# Display.net
KiCad netlist of a schematic drawn in Altium Designer
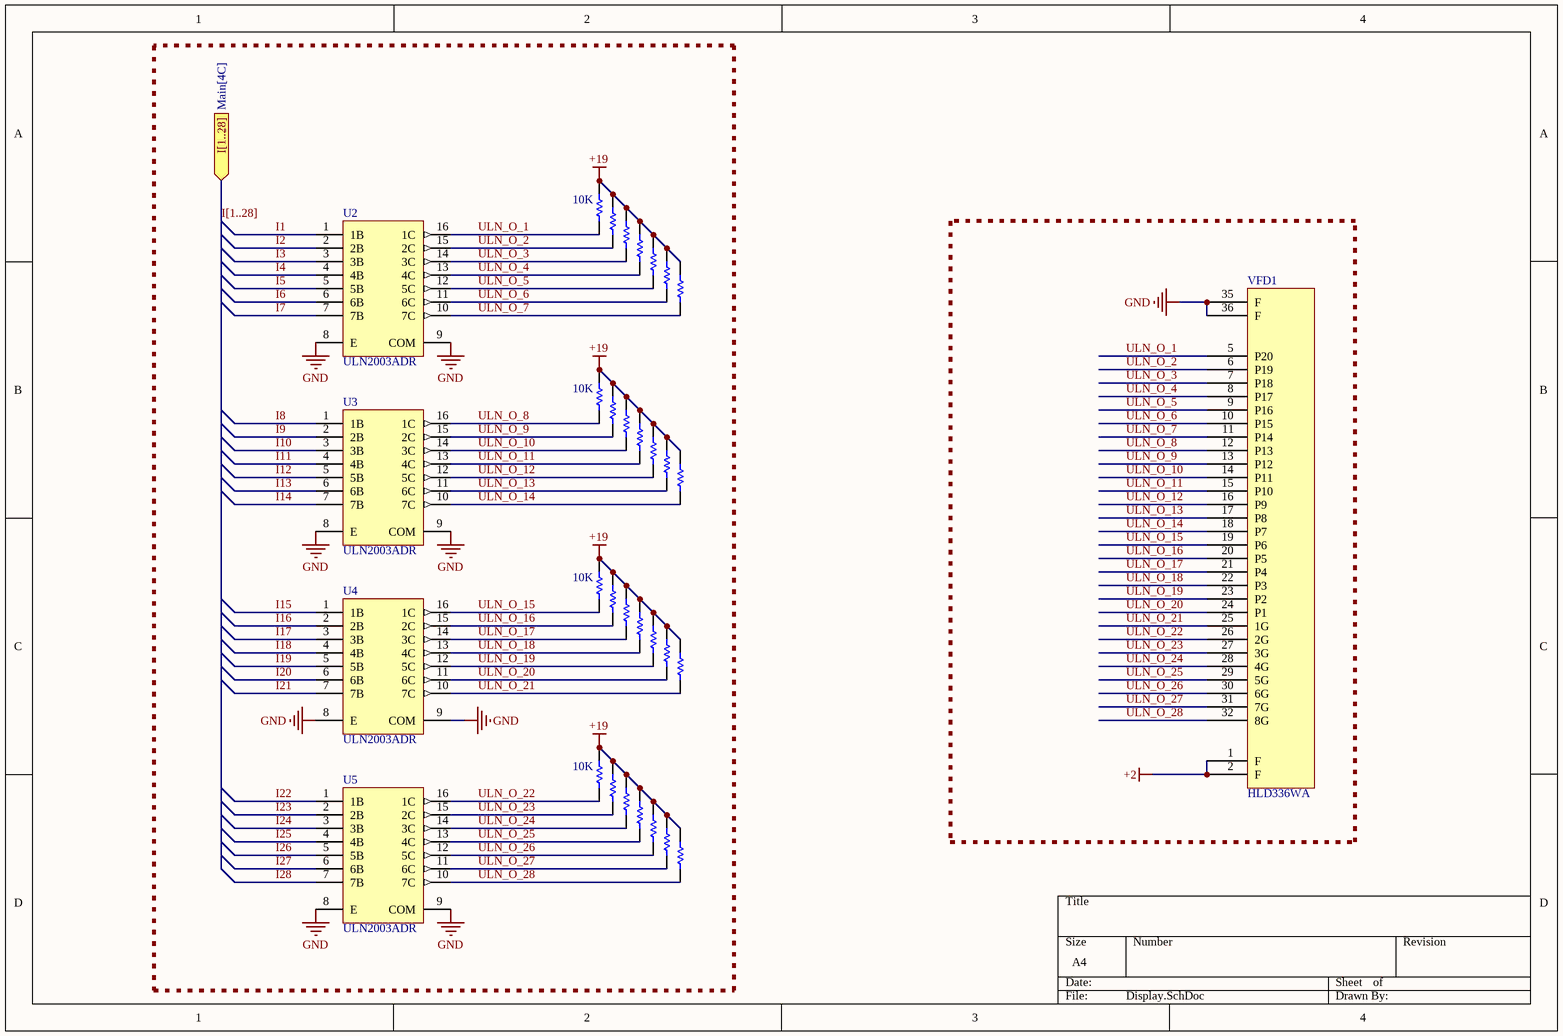
[diagram p0: Display.SchDoc]

(export (version "E")
  (design (tool "Eeschema 10.0.6"))
  (components
    (comp (ref "R4")
      (value "10K")
      (footprint "RESC1609X50X30ML10T20")
      (fields (field (name "MANUFACTURER") "Vishay Dale") (field (name "PART NUMBER") "CRCW060310K0FKTB"))
      (libsource (lib "Altium Content Vault") (part "RES"))
    )
    (comp (ref "R5")
      (value "10K")
      (footprint "RESC1609X50X30ML10T20")
      (fields (field (name "MANUFACTURER") "Vishay Dale") (field (name "PART NUMBER") "CRCW060310K0FKTB"))
      (libsource (lib "Altium Content Vault") (part "RES"))
    )
    (comp (ref "R6")
      (value "10K")
      (footprint "RESC1609X50X30ML10T20")
      (fields (field (name "MANUFACTURER") "Vishay Dale") (field (name "PART NUMBER") "CRCW060310K0FKTB"))
      (libsource (lib "Altium Content Vault") (part "RES"))
    )
    (comp (ref "R7")
      (value "10K")
      (footprint "RESC1609X50X30ML10T20")
      (fields (field (name "MANUFACTURER") "Vishay Dale") (field (name "PART NUMBER") "CRCW060310K0FKTB"))
      (libsource (lib "Altium Content Vault") (part "RES"))
    )
    (comp (ref "R8")
      (value "10K")
      (footprint "RESC1609X50X30ML10T20")
      (fields (field (name "MANUFACTURER") "Vishay Dale") (field (name "PART NUMBER") "CRCW060310K0FKTB"))
      (libsource (lib "Altium Content Vault") (part "RES"))
    )
    (comp (ref "R9")
      (value "10K")
      (footprint "RESC1609X50X30ML10T20")
      (fields (field (name "MANUFACTURER") "Vishay Dale") (field (name "PART NUMBER") "CRCW060310K0FKTB"))
      (libsource (lib "Altium Content Vault") (part "RES"))
    )
    (comp (ref "R10")
      (value "10K")
      (footprint "RESC1609X50X30ML10T20")
      (fields (field (name "MANUFACTURER") "Vishay Dale") (field (name "PART NUMBER") "CRCW060310K0FKTB"))
      (libsource (lib "Altium Content Vault") (part "RES"))
    )
    (comp (ref "R11")
      (value "10K")
      (footprint "RESC1609X50X30ML10T20")
      (fields (field (name "MANUFACTURER") "Vishay Dale") (field (name "PART NUMBER") "CRCW060310K0FKTB"))
      (libsource (lib "Altium Content Vault") (part "RES"))
    )
    (comp (ref "R12")
      (value "10K")
      (footprint "RESC1609X50X30ML10T20")
      (fields (field (name "MANUFACTURER") "Vishay Dale") (field (name "PART NUMBER") "CRCW060310K0FKTB"))
      (libsource (lib "Altium Content Vault") (part "RES"))
    )
    (comp (ref "R13")
      (value "10K")
      (footprint "RESC1609X50X30ML10T20")
      (fields (field (name "MANUFACTURER") "Vishay Dale") (field (name "PART NUMBER") "CRCW060310K0FKTB"))
      (libsource (lib "Altium Content Vault") (part "RES"))
    )
    (comp (ref "R14")
      (value "10K")
      (footprint "RESC1609X50X30ML10T20")
      (fields (field (name "MANUFACTURER") "Vishay Dale") (field (name "PART NUMBER") "CRCW060310K0FKTB"))
      (libsource (lib "Altium Content Vault") (part "RES"))
    )
    (comp (ref "R15")
      (value "10K")
      (footprint "RESC1609X50X30ML10T20")
      (fields (field (name "MANUFACTURER") "Vishay Dale") (field (name "PART NUMBER") "CRCW060310K0FKTB"))
      (libsource (lib "Altium Content Vault") (part "RES"))
    )
    (comp (ref "R16")
      (value "10K")
      (footprint "RESC1609X50X30ML10T20")
      (fields (field (name "MANUFACTURER") "Vishay Dale") (field (name "PART NUMBER") "CRCW060310K0FKTB"))
      (libsource (lib "Altium Content Vault") (part "RES"))
    )
    (comp (ref "R17")
      (value "10K")
      (footprint "RESC1609X50X30ML10T20")
      (fields (field (name "MANUFACTURER") "Vishay Dale") (field (name "PART NUMBER") "CRCW060310K0FKTB"))
      (libsource (lib "Altium Content Vault") (part "RES"))
    )
    (comp (ref "R18")
      (value "10K")
      (footprint "RESC1609X50X30ML10T20")
      (fields (field (name "MANUFACTURER") "Vishay Dale") (field (name "PART NUMBER") "CRCW060310K0FKTB"))
      (libsource (lib "Altium Content Vault") (part "RES"))
    )
    (comp (ref "R19")
      (value "10K")
      (footprint "RESC1609X50X30ML10T20")
      (fields (field (name "MANUFACTURER") "Vishay Dale") (field (name "PART NUMBER") "CRCW060310K0FKTB"))
      (libsource (lib "Altium Content Vault") (part "RES"))
    )
    (comp (ref "R20")
      (value "10K")
      (footprint "RESC1609X50X30ML10T20")
      (fields (field (name "MANUFACTURER") "Vishay Dale") (field (name "PART NUMBER") "CRCW060310K0FKTB"))
      (libsource (lib "Altium Content Vault") (part "RES"))
    )
    (comp (ref "R21")
      (value "10K")
      (footprint "RESC1609X50X30ML10T20")
      (fields (field (name "MANUFACTURER") "Vishay Dale") (field (name "PART NUMBER") "CRCW060310K0FKTB"))
      (libsource (lib "Altium Content Vault") (part "RES"))
    )
    (comp (ref "R22")
      (value "10K")
      (footprint "RESC1609X50X30ML10T20")
      (fields (field (name "MANUFACTURER") "Vishay Dale") (field (name "PART NUMBER") "CRCW060310K0FKTB"))
      (libsource (lib "Altium Content Vault") (part "RES"))
    )
    (comp (ref "R23")
      (value "10K")
      (footprint "RESC1609X50X30ML10T20")
      (fields (field (name "MANUFACTURER") "Vishay Dale") (field (name "PART NUMBER") "CRCW060310K0FKTB"))
      (libsource (lib "Altium Content Vault") (part "RES"))
    )
    (comp (ref "R24")
      (value "10K")
      (footprint "RESC1609X50X30ML10T20")
      (fields (field (name "MANUFACTURER") "Vishay Dale") (field (name "PART NUMBER") "CRCW060310K0FKTB"))
      (libsource (lib "Altium Content Vault") (part "RES"))
    )
    (comp (ref "R25")
      (value "10K")
      (footprint "RESC1609X50X30ML10T20")
      (fields (field (name "MANUFACTURER") "Vishay Dale") (field (name "PART NUMBER") "CRCW060310K0FKTB"))
      (libsource (lib "Altium Content Vault") (part "RES"))
    )
    (comp (ref "R26")
      (value "10K")
      (footprint "RESC1609X50X30ML10T20")
      (fields (field (name "MANUFACTURER") "Vishay Dale") (field (name "PART NUMBER") "CRCW060310K0FKTB"))
      (libsource (lib "Altium Content Vault") (part "RES"))
    )
    (comp (ref "R27")
      (value "10K")
      (footprint "RESC1609X50X30ML10T20")
      (fields (field (name "MANUFACTURER") "Vishay Dale") (field (name "PART NUMBER") "CRCW060310K0FKTB"))
      (libsource (lib "Altium Content Vault") (part "RES"))
    )
    (comp (ref "R28")
      (value "10K")
      (footprint "RESC1609X50X30ML10T20")
      (fields (field (name "MANUFACTURER") "Vishay Dale") (field (name "PART NUMBER") "CRCW060310K0FKTB"))
      (libsource (lib "Altium Content Vault") (part "RES"))
    )
    (comp (ref "R29")
      (value "10K")
      (footprint "RESC1609X50X30ML10T20")
      (fields (field (name "MANUFACTURER") "Vishay Dale") (field (name "PART NUMBER") "CRCW060310K0FKTB"))
      (libsource (lib "Altium Content Vault") (part "RES"))
    )
    (comp (ref "R30")
      (value "10K")
      (footprint "RESC1609X50X30ML10T20")
      (fields (field (name "MANUFACTURER") "Vishay Dale") (field (name "PART NUMBER") "CRCW060310K0FKTB"))
      (libsource (lib "Altium Content Vault") (part "RES"))
    )
    (comp (ref "R31")
      (value "10K")
      (footprint "RESC1609X50X30ML10T20")
      (fields (field (name "MANUFACTURER") "Vishay Dale") (field (name "PART NUMBER") "CRCW060310K0FKTB"))
      (libsource (lib "Altium Content Vault") (part "RES"))
    )
    (comp (ref "U2")
      (value "ULN2003ADR")
      (footprint "D0016A_M")
      (fields (field (name "MANUFACTURER") "TexasInstruments"))
      (libsource (lib "Altium Content Vault") (part "TI-ULX200X-D-16"))
    )
    (comp (ref "U3")
      (value "ULN2003ADR")
      (footprint "D0016A_M")
      (fields (field (name "MANUFACTURER") "TexasInstruments"))
      (libsource (lib "Altium Content Vault") (part "TI-ULX200X-D-16"))
    )
    (comp (ref "U4")
      (value "ULN2003ADR")
      (footprint "D0016A_M")
      (fields (field (name "MANUFACTURER") "TexasInstruments"))
      (libsource (lib "Altium Content Vault") (part "TI-ULX200X-D-16"))
    )
    (comp (ref "U5")
      (value "ULN2003ADR")
      (footprint "D0016A_M")
      (fields (field (name "MANUFACTURER") "TexasInstruments"))
      (libsource (lib "Altium Content Vault") (part "TI-ULX200X-D-16"))
    )
    (comp (ref "VFD1") (value "HLD336WA") (footprint "DIP72") (libsource (lib "HLD336WA") (part "HLD336WA")))
  )
  (nets
    (net (code "1") (name "+2") (class "Default")
      (node (ref "VFD1") (pin "1") (pinfunction "F_1") (pintype "passive"))
      (node (ref "VFD1") (pin "2") (pinfunction "F_2") (pintype "passive"))
    )
    (net (code "2") (name "+19") (class "Default")
      (node (ref "R10") (pin "1") (pinfunction "1_1") (pintype "passive"))
      (node (ref "R11") (pin "1") (pinfunction "1_1") (pintype "passive"))
      (node (ref "R12") (pin "1") (pinfunction "1_1") (pintype "passive"))
      (node (ref "R13") (pin "1") (pinfunction "1_1") (pintype "passive"))
      (node (ref "R14") (pin "1") (pinfunction "1_1") (pintype "passive"))
      (node (ref "R15") (pin "1") (pinfunction "1_1") (pintype "passive"))
      (node (ref "R16") (pin "1") (pinfunction "1_1") (pintype "passive"))
      (node (ref "R17") (pin "1") (pinfunction "1_1") (pintype "passive"))
      (node (ref "R18") (pin "1") (pinfunction "1_1") (pintype "passive"))
      (node (ref "R19") (pin "1") (pinfunction "1_1") (pintype "passive"))
      (node (ref "R20") (pin "1") (pinfunction "1_1") (pintype "passive"))
      (node (ref "R21") (pin "1") (pinfunction "1_1") (pintype "passive"))
      (node (ref "R22") (pin "1") (pinfunction "1_1") (pintype "passive"))
      (node (ref "R23") (pin "1") (pinfunction "1_1") (pintype "passive"))
      (node (ref "R24") (pin "1") (pinfunction "1_1") (pintype "passive"))
      (node (ref "R25") (pin "1") (pinfunction "1_1") (pintype "passive"))
      (node (ref "R26") (pin "1") (pinfunction "1_1") (pintype "passive"))
      (node (ref "R27") (pin "1") (pinfunction "1_1") (pintype "passive"))
      (node (ref "R28") (pin "1") (pinfunction "1_1") (pintype "passive"))
      (node (ref "R29") (pin "1") (pinfunction "1_1") (pintype "passive"))
      (node (ref "R30") (pin "1") (pinfunction "1_1") (pintype "passive"))
      (node (ref "R31") (pin "1") (pinfunction "1_1") (pintype "passive"))
      (node (ref "R4") (pin "1") (pinfunction "1_1") (pintype "passive"))
      (node (ref "R5") (pin "1") (pinfunction "1_1") (pintype "passive"))
      (node (ref "R6") (pin "1") (pinfunction "1_1") (pintype "passive"))
      (node (ref "R7") (pin "1") (pinfunction "1_1") (pintype "passive"))
      (node (ref "R8") (pin "1") (pinfunction "1_1") (pintype "passive"))
      (node (ref "R9") (pin "1") (pinfunction "1_1") (pintype "passive"))
    )
    (net (code "3") (name "/I1") (class "Default")
      (node (ref "U2") (pin "1") (pinfunction "1B_1") (pintype "passive"))
    )
    (net (code "4") (name "/I2") (class "Default")
      (node (ref "U2") (pin "2") (pinfunction "2B_2") (pintype "passive"))
    )
    (net (code "5") (name "/I3") (class "Default")
      (node (ref "U2") (pin "3") (pinfunction "3B_3") (pintype "passive"))
    )
    (net (code "6") (name "/I4") (class "Default")
      (node (ref "U2") (pin "4") (pinfunction "4B_4") (pintype "passive"))
    )
    (net (code "7") (name "/I5") (class "Default")
      (node (ref "U2") (pin "5") (pinfunction "5B_5") (pintype "passive"))
    )
    (net (code "8") (name "/I6") (class "Default")
      (node (ref "U2") (pin "6") (pinfunction "6B_6") (pintype "passive"))
    )
    (net (code "9") (name "/I7") (class "Default")
      (node (ref "U2") (pin "7") (pinfunction "7B_7") (pintype "passive"))
    )
    (net (code "10") (name "/I8") (class "Default")
      (node (ref "U3") (pin "1") (pinfunction "1B_1") (pintype "passive"))
    )
    (net (code "11") (name "/I9") (class "Default")
      (node (ref "U3") (pin "2") (pinfunction "2B_2") (pintype "passive"))
    )
    (net (code "12") (name "/I10") (class "Default")
      (node (ref "U3") (pin "3") (pinfunction "3B_3") (pintype "passive"))
    )
    (net (code "13") (name "/I11") (class "Default")
      (node (ref "U3") (pin "4") (pinfunction "4B_4") (pintype "passive"))
    )
    (net (code "14") (name "/I12") (class "Default")
      (node (ref "U3") (pin "5") (pinfunction "5B_5") (pintype "passive"))
    )
    (net (code "15") (name "/I13") (class "Default")
      (node (ref "U3") (pin "6") (pinfunction "6B_6") (pintype "passive"))
    )
    (net (code "16") (name "/I14") (class "Default")
      (node (ref "U3") (pin "7") (pinfunction "7B_7") (pintype "passive"))
    )
    (net (code "17") (name "/I15") (class "Default")
      (node (ref "U4") (pin "1") (pinfunction "1B_1") (pintype "passive"))
    )
    (net (code "18") (name "/I16") (class "Default")
      (node (ref "U4") (pin "2") (pinfunction "2B_2") (pintype "passive"))
    )
    (net (code "19") (name "/I17") (class "Default")
      (node (ref "U4") (pin "3") (pinfunction "3B_3") (pintype "passive"))
    )
    (net (code "20") (name "/I18") (class "Default")
      (node (ref "U4") (pin "4") (pinfunction "4B_4") (pintype "passive"))
    )
    (net (code "21") (name "/I19") (class "Default")
      (node (ref "U4") (pin "5") (pinfunction "5B_5") (pintype "passive"))
    )
    (net (code "22") (name "/I20") (class "Default")
      (node (ref "U4") (pin "6") (pinfunction "6B_6") (pintype "passive"))
    )
    (net (code "23") (name "/I21") (class "Default")
      (node (ref "U4") (pin "7") (pinfunction "7B_7") (pintype "passive"))
    )
    (net (code "24") (name "/I22") (class "Default")
      (node (ref "U5") (pin "1") (pinfunction "1B_1") (pintype "passive"))
    )
    (net (code "25") (name "/I23") (class "Default")
      (node (ref "U5") (pin "2") (pinfunction "2B_2") (pintype "passive"))
    )
    (net (code "26") (name "/I24") (class "Default")
      (node (ref "U5") (pin "3") (pinfunction "3B_3") (pintype "passive"))
    )
    (net (code "27") (name "/I25") (class "Default")
      (node (ref "U5") (pin "4") (pinfunction "4B_4") (pintype "passive"))
    )
    (net (code "28") (name "/I26") (class "Default")
      (node (ref "U5") (pin "5") (pinfunction "5B_5") (pintype "passive"))
    )
    (net (code "29") (name "/I27") (class "Default")
      (node (ref "U5") (pin "6") (pinfunction "6B_6") (pintype "passive"))
    )
    (net (code "30") (name "/I28") (class "Default")
      (node (ref "U5") (pin "7") (pinfunction "7B_7") (pintype "passive"))
    )
    (net (code "32") (name "/ULN_O_1") (class "Default")
      (node (ref "R5") (pin "2") (pinfunction "2_2") (pintype "passive"))
      (node (ref "U2") (pin "16") (pinfunction "1C_16") (pintype "output"))
      (node (ref "VFD1") (pin "5") (pinfunction "P20_5") (pintype "passive"))
    )
    (net (code "33") (name "/ULN_O_2") (class "Default")
      (node (ref "R6") (pin "2") (pinfunction "2_2") (pintype "passive"))
      (node (ref "U2") (pin "15") (pinfunction "2C_15") (pintype "output"))
      (node (ref "VFD1") (pin "6") (pinfunction "P19_6") (pintype "passive"))
    )
    (net (code "34") (name "/ULN_O_3") (class "Default")
      (node (ref "R7") (pin "2") (pinfunction "2_2") (pintype "passive"))
      (node (ref "U2") (pin "14") (pinfunction "3C_14") (pintype "output"))
      (node (ref "VFD1") (pin "7") (pinfunction "P18_7") (pintype "passive"))
    )
    (net (code "35") (name "/ULN_O_4") (class "Default")
      (node (ref "R8") (pin "2") (pinfunction "2_2") (pintype "passive"))
      (node (ref "U2") (pin "13") (pinfunction "4C_13") (pintype "output"))
      (node (ref "VFD1") (pin "8") (pinfunction "P17_8") (pintype "passive"))
    )
    (net (code "36") (name "/ULN_O_5") (class "Default")
      (node (ref "R9") (pin "2") (pinfunction "2_2") (pintype "passive"))
      (node (ref "U2") (pin "12") (pinfunction "5C_12") (pintype "output"))
      (node (ref "VFD1") (pin "9") (pinfunction "P16_9") (pintype "passive"))
    )
    (net (code "37") (name "/ULN_O_6") (class "Default")
      (node (ref "R10") (pin "2") (pinfunction "2_2") (pintype "passive"))
      (node (ref "U2") (pin "11") (pinfunction "6C_11") (pintype "output"))
      (node (ref "VFD1") (pin "10") (pinfunction "P15_10") (pintype "passive"))
    )
    (net (code "38") (name "/ULN_O_7") (class "Default")
      (node (ref "R11") (pin "2") (pinfunction "2_2") (pintype "passive"))
      (node (ref "U2") (pin "10") (pinfunction "7C_10") (pintype "output"))
      (node (ref "VFD1") (pin "11") (pinfunction "P14_11") (pintype "passive"))
    )
    (net (code "39") (name "/ULN_O_8") (class "Default")
      (node (ref "R12") (pin "2") (pinfunction "2_2") (pintype "passive"))
      (node (ref "U3") (pin "16") (pinfunction "1C_16") (pintype "output"))
      (node (ref "VFD1") (pin "12") (pinfunction "P13_12") (pintype "passive"))
    )
    (net (code "40") (name "/ULN_O_9") (class "Default")
      (node (ref "R13") (pin "2") (pinfunction "2_2") (pintype "passive"))
      (node (ref "U3") (pin "15") (pinfunction "2C_15") (pintype "output"))
      (node (ref "VFD1") (pin "13") (pinfunction "P12_13") (pintype "passive"))
    )
    (net (code "41") (name "/ULN_O_10") (class "Default")
      (node (ref "R14") (pin "2") (pinfunction "2_2") (pintype "passive"))
      (node (ref "U3") (pin "14") (pinfunction "3C_14") (pintype "output"))
      (node (ref "VFD1") (pin "14") (pinfunction "P11_14") (pintype "passive"))
    )
    (net (code "42") (name "/ULN_O_11") (class "Default")
      (node (ref "R15") (pin "2") (pinfunction "2_2") (pintype "passive"))
      (node (ref "U3") (pin "13") (pinfunction "4C_13") (pintype "output"))
      (node (ref "VFD1") (pin "15") (pinfunction "P10_15") (pintype "passive"))
    )
    (net (code "43") (name "/ULN_O_12") (class "Default")
      (node (ref "R16") (pin "2") (pinfunction "2_2") (pintype "passive"))
      (node (ref "U3") (pin "12") (pinfunction "5C_12") (pintype "output"))
      (node (ref "VFD1") (pin "16") (pinfunction "P9_16") (pintype "passive"))
    )
    (net (code "44") (name "/ULN_O_13") (class "Default")
      (node (ref "R17") (pin "2") (pinfunction "2_2") (pintype "passive"))
      (node (ref "U3") (pin "11") (pinfunction "6C_11") (pintype "output"))
      (node (ref "VFD1") (pin "17") (pinfunction "P8_17") (pintype "passive"))
    )
    (net (code "45") (name "/ULN_O_14") (class "Default")
      (node (ref "R18") (pin "2") (pinfunction "2_2") (pintype "passive"))
      (node (ref "U3") (pin "10") (pinfunction "7C_10") (pintype "output"))
      (node (ref "VFD1") (pin "18") (pinfunction "P7_18") (pintype "passive"))
    )
    (net (code "46") (name "/ULN_O_15") (class "Default")
      (node (ref "R19") (pin "2") (pinfunction "2_2") (pintype "passive"))
      (node (ref "U4") (pin "16") (pinfunction "1C_16") (pintype "output"))
      (node (ref "VFD1") (pin "19") (pinfunction "P6_19") (pintype "passive"))
    )
    (net (code "47") (name "/ULN_O_16") (class "Default")
      (node (ref "R20") (pin "2") (pinfunction "2_2") (pintype "passive"))
      (node (ref "U4") (pin "15") (pinfunction "2C_15") (pintype "output"))
      (node (ref "VFD1") (pin "20") (pinfunction "P5_20") (pintype "passive"))
    )
    (net (code "48") (name "/ULN_O_17") (class "Default")
      (node (ref "R21") (pin "2") (pinfunction "2_2") (pintype "passive"))
      (node (ref "U4") (pin "14") (pinfunction "3C_14") (pintype "output"))
      (node (ref "VFD1") (pin "21") (pinfunction "P4_21") (pintype "passive"))
    )
    (net (code "49") (name "/ULN_O_18") (class "Default")
      (node (ref "R22") (pin "2") (pinfunction "2_2") (pintype "passive"))
      (node (ref "U4") (pin "13") (pinfunction "4C_13") (pintype "output"))
      (node (ref "VFD1") (pin "22") (pinfunction "P3_22") (pintype "passive"))
    )
    (net (code "50") (name "/ULN_O_19") (class "Default")
      (node (ref "R23") (pin "2") (pinfunction "2_2") (pintype "passive"))
      (node (ref "U4") (pin "12") (pinfunction "5C_12") (pintype "output"))
      (node (ref "VFD1") (pin "23") (pinfunction "P2_23") (pintype "passive"))
    )
    (net (code "51") (name "/ULN_O_20") (class "Default")
      (node (ref "R24") (pin "2") (pinfunction "2_2") (pintype "passive"))
      (node (ref "U4") (pin "11") (pinfunction "6C_11") (pintype "output"))
      (node (ref "VFD1") (pin "24") (pinfunction "P1_24") (pintype "passive"))
    )
    (net (code "52") (name "/ULN_O_21") (class "Default")
      (node (ref "R4") (pin "2") (pinfunction "2_2") (pintype "passive"))
      (node (ref "U4") (pin "10") (pinfunction "7C_10") (pintype "output"))
      (node (ref "VFD1") (pin "25") (pinfunction "1G_25") (pintype "passive"))
    )
    (net (code "53") (name "/ULN_O_22") (class "Default")
      (node (ref "R25") (pin "2") (pinfunction "2_2") (pintype "passive"))
      (node (ref "U5") (pin "16") (pinfunction "1C_16") (pintype "output"))
      (node (ref "VFD1") (pin "26") (pinfunction "2G_26") (pintype "passive"))
    )
    (net (code "54") (name "/ULN_O_23") (class "Default")
      (node (ref "R26") (pin "2") (pinfunction "2_2") (pintype "passive"))
      (node (ref "U5") (pin "15") (pinfunction "2C_15") (pintype "output"))
      (node (ref "VFD1") (pin "27") (pinfunction "3G_27") (pintype "passive"))
    )
    (net (code "55") (name "/ULN_O_24") (class "Default")
      (node (ref "R27") (pin "2") (pinfunction "2_2") (pintype "passive"))
      (node (ref "U5") (pin "14") (pinfunction "3C_14") (pintype "output"))
      (node (ref "VFD1") (pin "28") (pinfunction "4G_28") (pintype "passive"))
    )
    (net (code "56") (name "/ULN_O_25") (class "Default")
      (node (ref "R28") (pin "2") (pinfunction "2_2") (pintype "passive"))
      (node (ref "U5") (pin "13") (pinfunction "4C_13") (pintype "output"))
      (node (ref "VFD1") (pin "29") (pinfunction "5G_29") (pintype "passive"))
    )
    (net (code "57") (name "/ULN_O_26") (class "Default")
      (node (ref "R29") (pin "2") (pinfunction "2_2") (pintype "passive"))
      (node (ref "U5") (pin "12") (pinfunction "5C_12") (pintype "output"))
      (node (ref "VFD1") (pin "30") (pinfunction "6G_30") (pintype "passive"))
    )
    (net (code "58") (name "/ULN_O_27") (class "Default")
      (node (ref "R30") (pin "2") (pinfunction "2_2") (pintype "passive"))
      (node (ref "U5") (pin "11") (pinfunction "6C_11") (pintype "output"))
      (node (ref "VFD1") (pin "31") (pinfunction "7G_31") (pintype "passive"))
    )
    (net (code "59") (name "/ULN_O_28") (class "Default")
      (node (ref "R31") (pin "2") (pinfunction "2_2") (pintype "passive"))
      (node (ref "U5") (pin "10") (pinfunction "7C_10") (pintype "output"))
      (node (ref "VFD1") (pin "32") (pinfunction "8G_32") (pintype "passive"))
    )
    (net (code "60") (name "GND") (class "Default")
      (node (ref "U2") (pin "8") (pinfunction "E_8") (pintype "passive"))
      (node (ref "U2") (pin "9") (pinfunction "COM_9") (pintype "passive"))
      (node (ref "U3") (pin "8") (pinfunction "E_8") (pintype "passive"))
      (node (ref "U3") (pin "9") (pinfunction "COM_9") (pintype "passive"))
      (node (ref "U4") (pin "8") (pinfunction "E_8") (pintype "passive"))
      (node (ref "U4") (pin "9") (pinfunction "COM_9") (pintype "passive"))
      (node (ref "U5") (pin "8") (pinfunction "E_8") (pintype "passive"))
      (node (ref "U5") (pin "9") (pinfunction "COM_9") (pintype "passive"))
      (node (ref "VFD1") (pin "35") (pinfunction "F_35") (pintype "passive"))
      (node (ref "VFD1") (pin "36") (pinfunction "F_36") (pintype "passive"))
    )
  )
)
